# FW2-01-FlashingLED.net
KiCad netlist of a schematic drawn in EAGLE
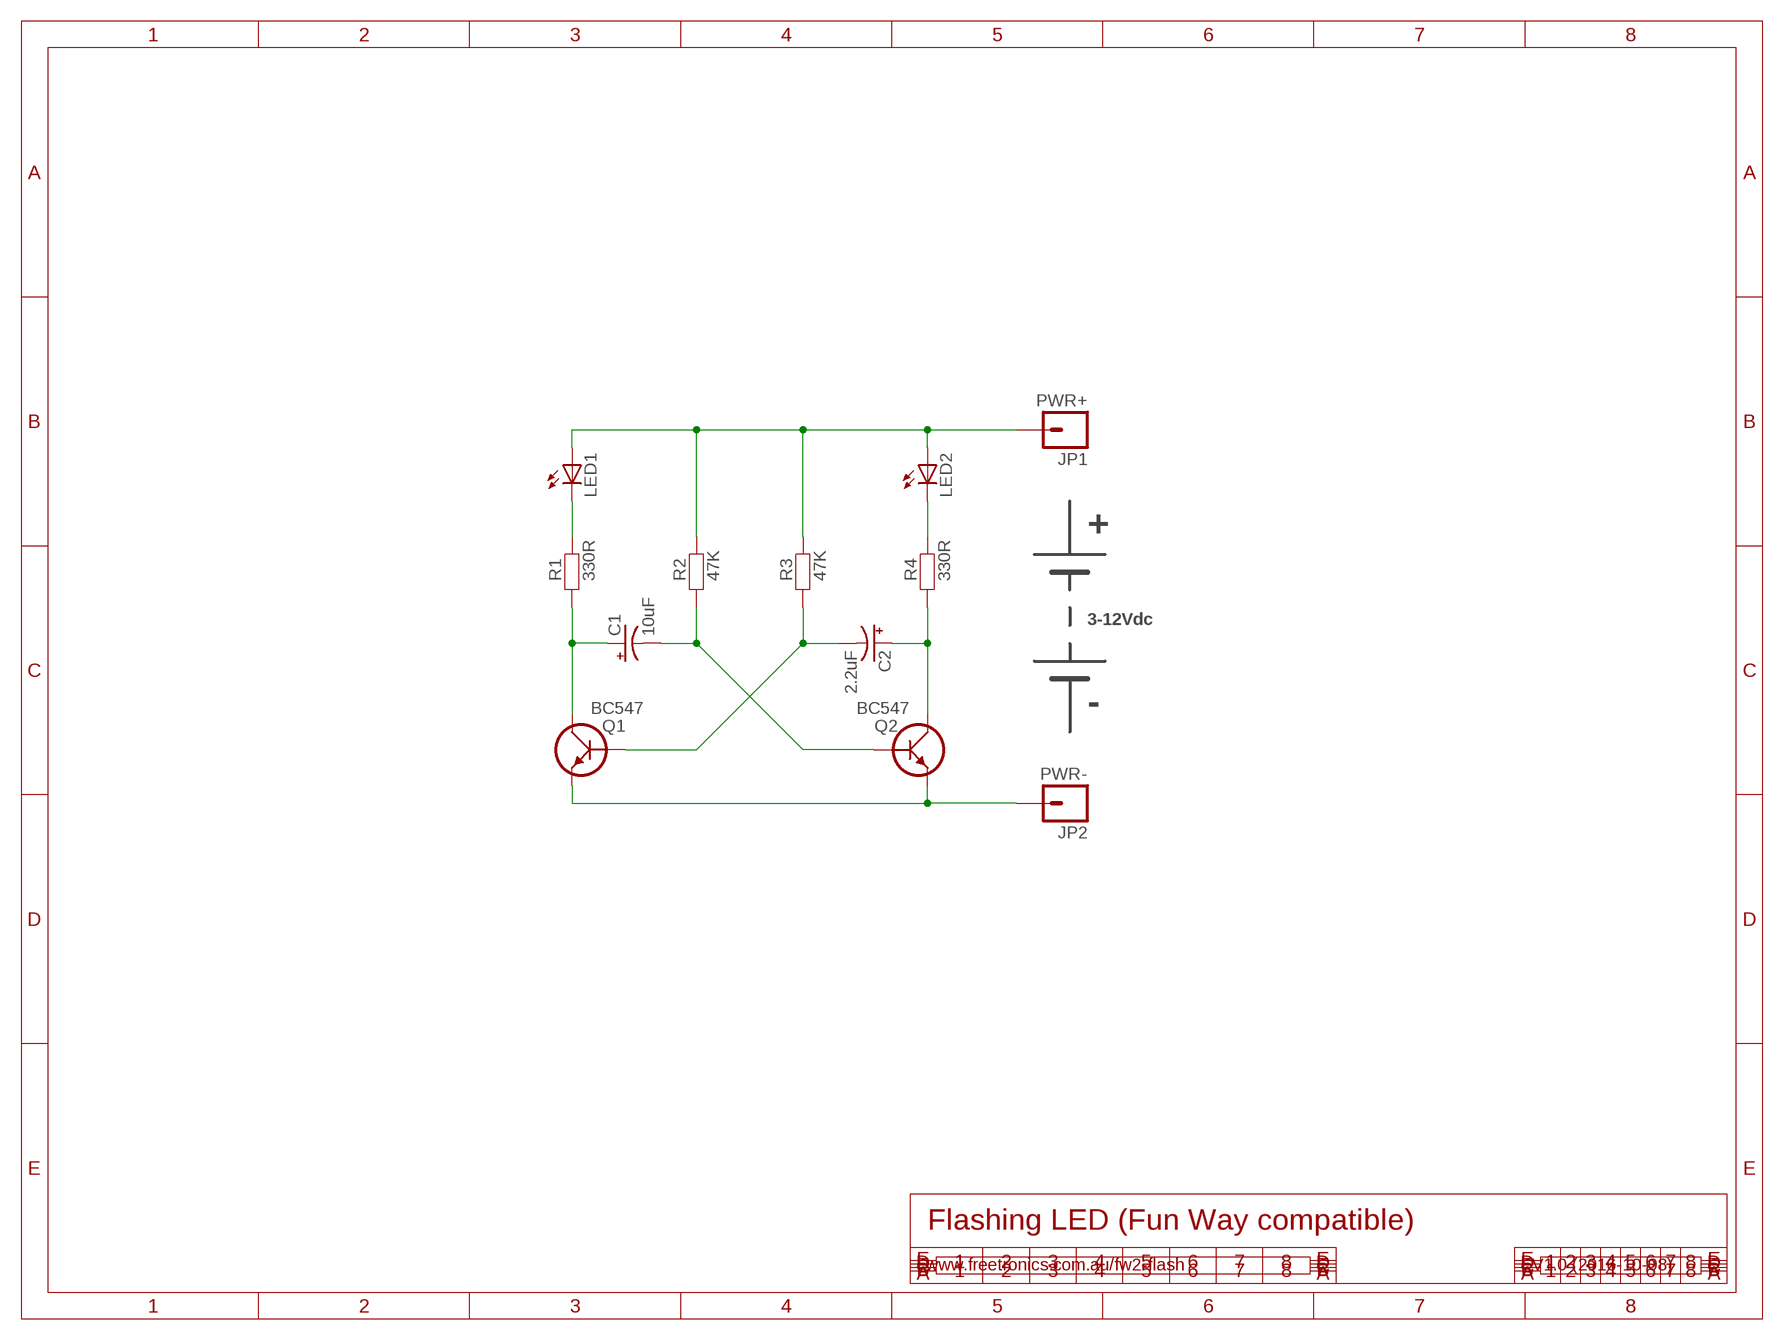
[diagram p0: schematic, sheet 1]

(export (version "E")
  (design (tool "Eeschema 10.0.6"))
  (components
    (comp (ref "C1")
      (value "10uF")
      (footprint "eagle-import:E5-5")
      (libsource (lib "eagle-import") (part "CPOL-USE5-5"))
    )
    (comp (ref "C2")
      (value "2.2uF")
      (footprint "eagle-import:E5-5")
      (libsource (lib "eagle-import") (part "CPOL-USE5-5"))
    )
    (comp (ref "JP1")
      (value "PWR+")
      (footprint "eagle-import:1X01")
      (libsource (lib "eagle-import") (part "M01PTH"))
    )
    (comp (ref "JP2")
      (value "PWR-")
      (footprint "eagle-import:1X01")
      (libsource (lib "eagle-import") (part "M01PTH"))
    )
    (comp (ref "LED1")
      (value "LED5MM")
      (footprint "eagle-import:LED5MM")
      (libsource (lib "eagle-import") (part "LED5MM"))
    )
    (comp (ref "LED2")
      (value "LED5MM")
      (footprint "eagle-import:LED5MM")
      (libsource (lib "eagle-import") (part "LED5MM"))
    )
    (comp (ref "Q1")
      (value "BC547")
      (footprint "eagle-import:TO-92")
      (libsource (lib "eagle-import") (part "BC547"))
    )
    (comp (ref "Q2")
      (value "BC547")
      (footprint "eagle-import:TO-92")
      (libsource (lib "eagle-import") (part "BC547"))
    )
    (comp (ref "R1")
      (value "330R")
      (footprint "eagle-import:FREETRONICS_AXIAL-0.4")
      (libsource (lib "eagle-import") (part "FREETRONICS_RESISTORPTH2"))
    )
    (comp (ref "R2")
      (value "47K")
      (footprint "eagle-import:FREETRONICS_AXIAL-0.4")
      (libsource (lib "eagle-import") (part "FREETRONICS_RESISTORPTH2"))
    )
    (comp (ref "R3")
      (value "47K")
      (footprint "eagle-import:FREETRONICS_AXIAL-0.4")
      (libsource (lib "eagle-import") (part "FREETRONICS_RESISTORPTH2"))
    )
    (comp (ref "R4")
      (value "330R")
      (footprint "eagle-import:FREETRONICS_AXIAL-0.4")
      (libsource (lib "eagle-import") (part "FREETRONICS_RESISTORPTH2"))
    )
  )
  (nets
    (net (code "1") (name "Net-(LED1-C)") (class "Default")
      (node (ref "LED1") (pin "K") (pinfunction "C_K") (pintype "passive"))
      (node (ref "R1") (pin "P$2") (pinfunction "2_P$2") (pintype "passive"))
    )
    (net (code "2") (name "Net-(LED2-C)") (class "Default")
      (node (ref "LED2") (pin "K") (pinfunction "C_K") (pintype "passive"))
      (node (ref "R4") (pin "P$2") (pinfunction "2_P$2") (pintype "passive"))
    )
    (net (code "3") (name "Net-(Q1-B)") (class "Default")
      (node (ref "C2") (pin "-") (pinfunction "-_-") (pintype "passive"))
      (node (ref "Q1") (pin "2") (pinfunction "B_2") (pintype "passive"))
      (node (ref "R3") (pin "P$1") (pinfunction "1_P$1") (pintype "passive"))
    )
    (net (code "4") (name "Net-(Q1-C)") (class "Default")
      (node (ref "C1") (pin "+") (pinfunction "+_+") (pintype "passive"))
      (node (ref "Q1") (pin "1") (pinfunction "C_1") (pintype "passive"))
      (node (ref "R1") (pin "P$1") (pinfunction "1_P$1") (pintype "passive"))
    )
    (net (code "5") (name "Net-(Q1-E)") (class "Default")
      (node (ref "JP2") (pin "1") (pinfunction "1_1") (pintype "passive"))
      (node (ref "Q1") (pin "3") (pinfunction "E_3") (pintype "passive"))
      (node (ref "Q2") (pin "3") (pinfunction "E_3") (pintype "passive"))
    )
    (net (code "6") (name "Net-(Q2-B)") (class "Default")
      (node (ref "C1") (pin "-") (pinfunction "-_-") (pintype "passive"))
      (node (ref "Q2") (pin "2") (pinfunction "B_2") (pintype "passive"))
      (node (ref "R2") (pin "P$1") (pinfunction "1_P$1") (pintype "passive"))
    )
    (net (code "7") (name "Net-(Q2-C)") (class "Default")
      (node (ref "C2") (pin "+") (pinfunction "+_+") (pintype "passive"))
      (node (ref "Q2") (pin "1") (pinfunction "C_1") (pintype "passive"))
      (node (ref "R4") (pin "P$1") (pinfunction "1_P$1") (pintype "passive"))
    )
    (net (code "8") (name "Net-(R2-2)") (class "Default")
      (node (ref "JP1") (pin "1") (pinfunction "1_1") (pintype "passive"))
      (node (ref "LED1") (pin "A") (pinfunction "A_A") (pintype "passive"))
      (node (ref "LED2") (pin "A") (pinfunction "A_A") (pintype "passive"))
      (node (ref "R2") (pin "P$2") (pinfunction "2_P$2") (pintype "passive"))
      (node (ref "R3") (pin "P$2") (pinfunction "2_P$2") (pintype "passive"))
    )
  )
)
